# 555TimerOrganFinal.net
KiCad netlist of a schematic drawn in Altium Designer
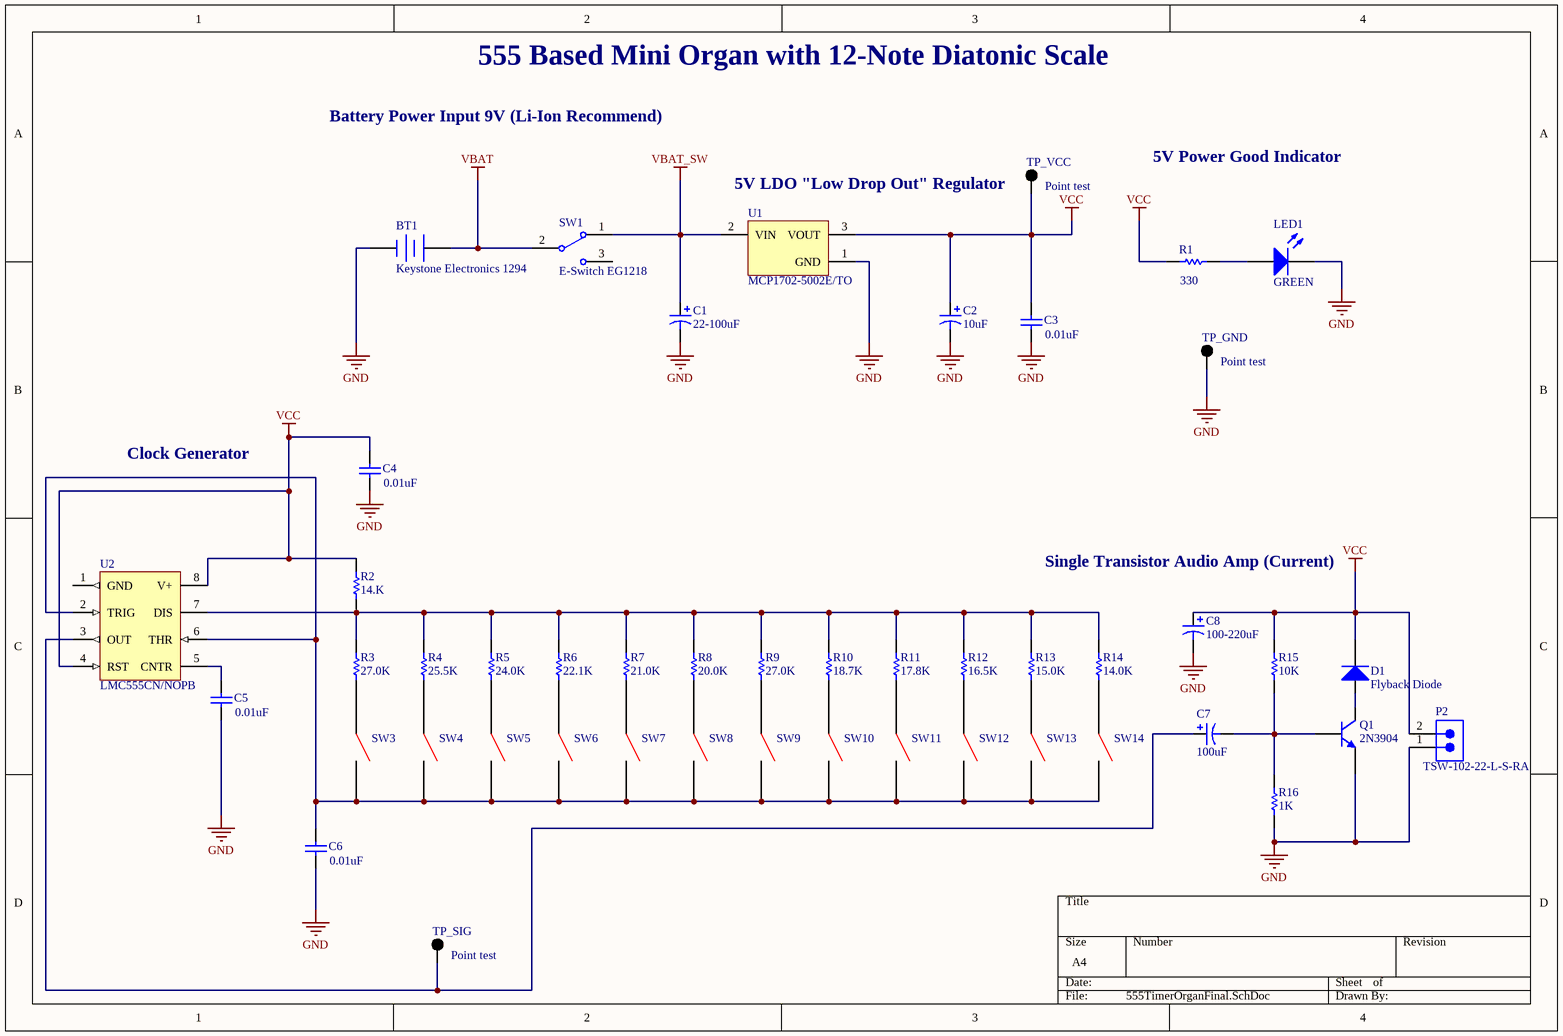
[diagram p0: 555TimerOrganFinal.SchDoc]

(export (version "E")
  (design (tool "Eeschema 10.0.6"))
  (components
    (comp (ref "BT1")
      (value "Keystone Electronics 1294")
      (footprint "PCB-3798-1")
      (description "HOLDER BATT 9V UNIV PLASTIC PC")
      (fields (field (name "MANUFACTURER PART NUMBER") "1294"))
      (libsource (lib "My Personal Space") (part "SYM-3798-1"))
    )
    (comp (ref "C1")
      (value "22-100uF")
      (footprint "PCB-nq6yd78wv7rl8ojp8omb-1")
      (description "Cap Aluminum 10uF 16V 20% (4 X 7mm) Cylindrical 18mA 7000 hr 105°C T/R")
      (fields (field (name "MANUFACTURER PART NUMBER") "UCB1C100MCL1GS"))
      (libsource (lib "My Personal Space") (part "SYM-119dd9bbe86bce5a-1"))
    )
    (comp (ref "C2")
      (value "10uF")
      (footprint "PCB-nq6yd78wv7rl8ojp8omb-1")
      (description "Cap Aluminum 10uF 16V 20% (4 X 7mm) Cylindrical 18mA 7000 hr 105°C T/R")
      (fields (field (name "MANUFACTURER PART NUMBER") "UCB1C100MCL1GS"))
      (libsource (lib "My Personal Space") (part "SYM-119dd9bbe86bce5a-1"))
    )
    (comp (ref "C3")
      (value "0.01uF")
      (footprint "PCB-ql28fbuo3tond8refhb5-1")
      (description "K 100nF Ceramic Multilayer Capacitor, 50 V dc, +125degC, X7R Dielectric, +/-10%")
      (libsource (lib "My Personal Space") (part "SYM-1272d9258f2acdb5-2"))
    )
    (comp (ref "C4")
      (value "0.01uF")
      (footprint "PCB-ql28fbuo3tond8refhb5-1")
      (description "K 100nF Ceramic Multilayer Capacitor, 50 V dc, +125degC, X7R Dielectric, +/-10%")
      (libsource (lib "My Personal Space") (part "SYM-1272d9258f2acdb5-2"))
    )
    (comp (ref "C5")
      (value "0.01uF")
      (footprint "PCB-ql28fbuo3tond8refhb5-1")
      (description "K 100nF Ceramic Multilayer Capacitor, 50 V dc, +125degC, X7R Dielectric, +/-10%")
      (libsource (lib "My Personal Space") (part "SYM-1272d9258f2acdb5-2"))
    )
    (comp (ref "C6")
      (value "0.01uF")
      (footprint "PCB-ql28fbuo3tond8refhb5-1")
      (description "K 100nF Ceramic Multilayer Capacitor, 50 V dc, +125degC, X7R Dielectric, +/-10%")
      (libsource (lib "My Personal Space") (part "SYM-1272d9258f2acdb5-2"))
    )
    (comp (ref "C7")
      (value "100uF")
      (footprint "PCB-nq6yd78wv7rl8ojp8omb-1")
      (description "Cap Aluminum 10uF 16V 20% (4 X 7mm) Cylindrical 18mA 7000 hr 105°C T/R")
      (fields (field (name "MANUFACTURER PART NUMBER") "UCB1C100MCL1GS"))
      (libsource (lib "My Personal Space") (part "SYM-119dd9bbe86bce5a-1"))
    )
    (comp (ref "C8")
      (value "100-220uF")
      (footprint "PCB-nq6yd78wv7rl8ojp8omb-1")
      (description "Cap Aluminum 10uF 16V 20% (4 X 7mm) Cylindrical 18mA 7000 hr 105°C T/R")
      (fields (field (name "MANUFACTURER PART NUMBER") "UCB1C100MCL1GS"))
      (libsource (lib "My Personal Space") (part "SYM-119dd9bbe86bce5a-1"))
    )
    (comp (ref "D1")
      (value "Flyback Diode")
      (footprint "PCB-z2ypi7zr74mzpyjelpsh-1")
      (description "Standard Recovery Rectifier, 2-Pin Axial_Lead, Pb-Free, Tape and Reel")
      (fields (field (name "MANUFACTURER PART NUMBER") "1N4001RLG"))
      (libsource (lib "My Personal Space") (part "SYM-e02d2927e6e83fea-1"))
    )
    (comp (ref "LED1")
      (value "GREEN")
      (footprint "PCB-b5vk7vz0xhkw7l0fnova-1")
      (description "LED Uni-Color Green 2-Pin T-1 3/4 Bulk")
      (fields
        (field (name "MANUFACTURER PART NUMBER") "C503B-GCN-CY0C0791")
        (field (name "MANUFACTURER") "Cree")
      )
      (libsource (lib "My Personal Space") (part "SYM-92bb5b2eff764d7c-1"))
    )
    (comp (ref "P2")
      (value "TSW-102-22-L-S-RA")
      (footprint "SMTC-TSW-102-22-X-S-RA")
      (libsource (lib "My Personal Space") (part "SMTC-TSW-102-X-X-S-X"))
    )
    (comp (ref "Q1")
      (value "2N3904")
      (footprint "PCB-d52vzgbszc9onplxz1b0-1")
      (description "Transistor General Purpose BJT NPN 40 Volt 0.2 Amp 3-Pin TO-92 Tape And Reel")
      (fields (field (name "MANUFACTURER PART NUMBER") "2N3904TF"))
      (libsource (lib "My Personal Space") (part "2N3904"))
    )
    (comp (ref "R1")
      (value "330")
      (footprint "PCB-0jk5y5qyb1smy9vf6b7t-1")
      (description "Res, 1K, 250mW, 5%, Axial")
      (libsource (lib "My Personal Space") (part "SYM-db3e1311f37e04f9-4"))
    )
    (comp (ref "R2")
      (value "14.K")
      (footprint "PCB-0jk5y5qyb1smy9vf6b7t-1")
      (description "Res, 1K, 250mW, 5%, Axial")
      (libsource (lib "My Personal Space") (part "SYM-db3e1311f37e04f9-4"))
    )
    (comp (ref "R3")
      (value "27.0K")
      (footprint "PCB-0jk5y5qyb1smy9vf6b7t-1")
      (description "Res, 1K, 250mW, 5%, Axial")
      (libsource (lib "My Personal Space") (part "SYM-db3e1311f37e04f9-4"))
    )
    (comp (ref "R4")
      (value "25.5K")
      (footprint "PCB-0jk5y5qyb1smy9vf6b7t-1")
      (description "Res, 1K, 250mW, 5%, Axial")
      (libsource (lib "My Personal Space") (part "SYM-db3e1311f37e04f9-4"))
    )
    (comp (ref "R5")
      (value "24.0K")
      (footprint "PCB-0jk5y5qyb1smy9vf6b7t-1")
      (description "Res, 1K, 250mW, 5%, Axial")
      (libsource (lib "My Personal Space") (part "SYM-db3e1311f37e04f9-4"))
    )
    (comp (ref "R6")
      (value "22.1K")
      (footprint "PCB-0jk5y5qyb1smy9vf6b7t-1")
      (description "Res, 1K, 250mW, 5%, Axial")
      (libsource (lib "My Personal Space") (part "SYM-db3e1311f37e04f9-4"))
    )
    (comp (ref "R7")
      (value "21.0K")
      (footprint "PCB-0jk5y5qyb1smy9vf6b7t-1")
      (description "Res, 1K, 250mW, 5%, Axial")
      (libsource (lib "My Personal Space") (part "SYM-db3e1311f37e04f9-4"))
    )
    (comp (ref "R8")
      (value "20.0K")
      (footprint "PCB-0jk5y5qyb1smy9vf6b7t-1")
      (description "Res, 1K, 250mW, 5%, Axial")
      (libsource (lib "My Personal Space") (part "SYM-db3e1311f37e04f9-4"))
    )
    (comp (ref "R9")
      (value "27.0K")
      (footprint "PCB-0jk5y5qyb1smy9vf6b7t-1")
      (description "Res, 1K, 250mW, 5%, Axial")
      (libsource (lib "My Personal Space") (part "SYM-db3e1311f37e04f9-4"))
    )
    (comp (ref "R10")
      (value "18.7K")
      (footprint "PCB-0jk5y5qyb1smy9vf6b7t-1")
      (description "Res, 1K, 250mW, 5%, Axial")
      (libsource (lib "My Personal Space") (part "SYM-db3e1311f37e04f9-4"))
    )
    (comp (ref "R11")
      (value "17.8K")
      (footprint "PCB-0jk5y5qyb1smy9vf6b7t-1")
      (description "Res, 1K, 250mW, 5%, Axial")
      (libsource (lib "My Personal Space") (part "SYM-db3e1311f37e04f9-4"))
    )
    (comp (ref "R12")
      (value "16.5K")
      (footprint "PCB-0jk5y5qyb1smy9vf6b7t-1")
      (description "Res, 1K, 250mW, 5%, Axial")
      (libsource (lib "My Personal Space") (part "SYM-db3e1311f37e04f9-4"))
    )
    (comp (ref "R13")
      (value "15.0K")
      (footprint "PCB-0jk5y5qyb1smy9vf6b7t-1")
      (description "Res, 1K, 250mW, 5%, Axial")
      (libsource (lib "My Personal Space") (part "SYM-db3e1311f37e04f9-4"))
    )
    (comp (ref "R14")
      (value "14.0K")
      (footprint "PCB-0jk5y5qyb1smy9vf6b7t-1")
      (description "Res, 1K, 250mW, 5%, Axial")
      (libsource (lib "My Personal Space") (part "SYM-db3e1311f37e04f9-4"))
    )
    (comp (ref "R15")
      (value "10K")
      (footprint "PCB-0jk5y5qyb1smy9vf6b7t-1")
      (description "Res, 1K, 250mW, 5%, Axial")
      (libsource (lib "My Personal Space") (part "SYM-db3e1311f37e04f9-4"))
    )
    (comp (ref "R16")
      (value "1K")
      (footprint "PCB-0jk5y5qyb1smy9vf6b7t-1")
      (description "Res, 1K, 250mW, 5%, Axial")
      (libsource (lib "My Personal Space") (part "SYM-db3e1311f37e04f9-4"))
    )
    (comp (ref "SW1")
      (value "E-Switch EG1218")
      (footprint "ESWI-EG1218_V")
      (description "Slide Switch, 500 V, -20 to 70 degC, 3-Pin THD, RoHS")
      (fields (field (name "MANUFACTURER PART NUMBER") "EG1218"))
      (libsource (lib "My Personal Space") (part "SW-SPDT-3_B"))
    )
    (comp (ref "SW3")
      (value "~")
      (footprint "PCB-je10m8m3eogq13l465bo-1")
      (description "Switch Tactile N.O. SPST Round Button PC Pins 0.02A 15VDC 1.3N Thru-Hole Radial T/R")
      (fields
        (field (name "ELEMENT14 PART NO.") "2281982")
        (field (name "MANUFACTURER PART NUMBER") "EVQ-21405R")
      )
      (libsource (lib "My Personal Space") (part "SYM-2fe5e5be239cf022-1"))
    )
    (comp (ref "SW4")
      (value "~")
      (footprint "PCB-je10m8m3eogq13l465bo-1")
      (description "Switch Tactile N.O. SPST Round Button PC Pins 0.02A 15VDC 1.3N Thru-Hole Radial T/R")
      (fields
        (field (name "ELEMENT14 PART NO.") "2281982")
        (field (name "MANUFACTURER PART NUMBER") "EVQ-21405R")
      )
      (libsource (lib "My Personal Space") (part "SYM-2fe5e5be239cf022-1"))
    )
    (comp (ref "SW5")
      (value "~")
      (footprint "PCB-je10m8m3eogq13l465bo-1")
      (description "Switch Tactile N.O. SPST Round Button PC Pins 0.02A 15VDC 1.3N Thru-Hole Radial T/R")
      (fields
        (field (name "ELEMENT14 PART NO.") "2281982")
        (field (name "MANUFACTURER PART NUMBER") "EVQ-21405R")
      )
      (libsource (lib "My Personal Space") (part "SYM-2fe5e5be239cf022-1"))
    )
    (comp (ref "SW6")
      (value "~")
      (footprint "PCB-je10m8m3eogq13l465bo-1")
      (description "Switch Tactile N.O. SPST Round Button PC Pins 0.02A 15VDC 1.3N Thru-Hole Radial T/R")
      (fields
        (field (name "ELEMENT14 PART NO.") "2281982")
        (field (name "MANUFACTURER PART NUMBER") "EVQ-21405R")
      )
      (libsource (lib "My Personal Space") (part "SYM-2fe5e5be239cf022-1"))
    )
    (comp (ref "SW7")
      (value "~")
      (footprint "PCB-je10m8m3eogq13l465bo-1")
      (description "Switch Tactile N.O. SPST Round Button PC Pins 0.02A 15VDC 1.3N Thru-Hole Radial T/R")
      (fields
        (field (name "ELEMENT14 PART NO.") "2281982")
        (field (name "MANUFACTURER PART NUMBER") "EVQ-21405R")
      )
      (libsource (lib "My Personal Space") (part "SYM-2fe5e5be239cf022-1"))
    )
    (comp (ref "SW8")
      (value "~")
      (footprint "PCB-je10m8m3eogq13l465bo-1")
      (description "Switch Tactile N.O. SPST Round Button PC Pins 0.02A 15VDC 1.3N Thru-Hole Radial T/R")
      (fields
        (field (name "ELEMENT14 PART NO.") "2281982")
        (field (name "MANUFACTURER PART NUMBER") "EVQ-21405R")
      )
      (libsource (lib "My Personal Space") (part "SYM-2fe5e5be239cf022-1"))
    )
    (comp (ref "SW9")
      (value "~")
      (footprint "PCB-je10m8m3eogq13l465bo-1")
      (description "Switch Tactile N.O. SPST Round Button PC Pins 0.02A 15VDC 1.3N Thru-Hole Radial T/R")
      (fields
        (field (name "ELEMENT14 PART NO.") "2281982")
        (field (name "MANUFACTURER PART NUMBER") "EVQ-21405R")
      )
      (libsource (lib "My Personal Space") (part "SYM-2fe5e5be239cf022-1"))
    )
    (comp (ref "SW10")
      (value "~")
      (footprint "PCB-je10m8m3eogq13l465bo-1")
      (description "Switch Tactile N.O. SPST Round Button PC Pins 0.02A 15VDC 1.3N Thru-Hole Radial T/R")
      (fields
        (field (name "ELEMENT14 PART NO.") "2281982")
        (field (name "MANUFACTURER PART NUMBER") "EVQ-21405R")
      )
      (libsource (lib "My Personal Space") (part "SYM-2fe5e5be239cf022-1"))
    )
    (comp (ref "SW11")
      (value "~")
      (footprint "PCB-je10m8m3eogq13l465bo-1")
      (description "Switch Tactile N.O. SPST Round Button PC Pins 0.02A 15VDC 1.3N Thru-Hole Radial T/R")
      (fields
        (field (name "ELEMENT14 PART NO.") "2281982")
        (field (name "MANUFACTURER PART NUMBER") "EVQ-21405R")
      )
      (libsource (lib "My Personal Space") (part "SYM-2fe5e5be239cf022-1"))
    )
    (comp (ref "SW12")
      (value "~")
      (footprint "PCB-je10m8m3eogq13l465bo-1")
      (description "Switch Tactile N.O. SPST Round Button PC Pins 0.02A 15VDC 1.3N Thru-Hole Radial T/R")
      (fields
        (field (name "ELEMENT14 PART NO.") "2281982")
        (field (name "MANUFACTURER PART NUMBER") "EVQ-21405R")
      )
      (libsource (lib "My Personal Space") (part "SYM-2fe5e5be239cf022-1"))
    )
    (comp (ref "SW13")
      (value "~")
      (footprint "PCB-je10m8m3eogq13l465bo-1")
      (description "Switch Tactile N.O. SPST Round Button PC Pins 0.02A 15VDC 1.3N Thru-Hole Radial T/R")
      (fields
        (field (name "ELEMENT14 PART NO.") "2281982")
        (field (name "MANUFACTURER PART NUMBER") "EVQ-21405R")
      )
      (libsource (lib "My Personal Space") (part "SYM-2fe5e5be239cf022-1"))
    )
    (comp (ref "SW14")
      (value "~")
      (footprint "PCB-je10m8m3eogq13l465bo-1")
      (description "Switch Tactile N.O. SPST Round Button PC Pins 0.02A 15VDC 1.3N Thru-Hole Radial T/R")
      (fields
        (field (name "ELEMENT14 PART NO.") "2281982")
        (field (name "MANUFACTURER PART NUMBER") "EVQ-21405R")
      )
      (libsource (lib "My Personal Space") (part "SYM-2fe5e5be239cf022-1"))
    )
    (comp (ref "TP_GND")
      (value "Point test")
      (footprint "P1-09")
      (description "KEYSTONE   5001   TEST POINT, PCB, THROUGH HOLE")
      (libsource (lib "My Personal Space") (part "KSTN-5001"))
    )
    (comp (ref "TP_SIG")
      (value "Point test")
      (footprint "P1-09")
      (description "KEYSTONE   5001   TEST POINT, PCB, THROUGH HOLE")
      (libsource (lib "My Personal Space") (part "KSTN-5001"))
    )
    (comp (ref "TP_VCC")
      (value "Point test")
      (footprint "P1-09")
      (description "KEYSTONE   5001   TEST POINT, PCB, THROUGH HOLE")
      (libsource (lib "My Personal Space") (part "KSTN-5001"))
    )
    (comp (ref "U1")
      (value "MCP1702-5002E/TO")
      (footprint "TO-92-TO3")
      (description "250 mA Low Quiescent Current LDO Regulator, 3-Pin TO-92, Extended TemperatureBAG")
      (libsource (lib "My Personal Space") (part "PM-LINEREG-MCP1702-IL3A"))
    )
    (comp (ref "U2")
      (value "LMC555CN/NOPB")
      (footprint "TI-D8_L")
      (description "World’s smallest 555 timer with low power, high accuracy and a Fmax of 3MHz 8-SOIC -40 to 85")
      (fields (field (name "MANUFACTURER PART NUMBER") "LMC555CMX/NOPB"))
      (libsource (lib "My Personal Space") (part "INF-TLE5012BE5000-PG-DSO-8-16-8"))
    )
  )
  (nets
    (net (code "1") (name "GND") (class "Default")
      (node (ref "BT1") (pin "2") (pinfunction "-_2") (pintype "passive"))
      (node (ref "C1") (pin "2") (pinfunction "2_2") (pintype "passive"))
      (node (ref "C2") (pin "2") (pinfunction "2_2") (pintype "passive"))
      (node (ref "C3") (pin "1") (pinfunction "1_1") (pintype "passive"))
      (node (ref "C4") (pin "1") (pinfunction "1_1") (pintype "passive"))
      (node (ref "C5") (pin "1") (pinfunction "1_1") (pintype "passive"))
      (node (ref "C6") (pin "1") (pinfunction "1_1") (pintype "passive"))
      (node (ref "C8") (pin "2") (pinfunction "2_2") (pintype "passive"))
      (node (ref "LED1") (pin "1") (pinfunction "K_1") (pintype "passive"))
      (node (ref "P2") (pin "1") (pinfunction "1_1") (pintype "passive"))
      (node (ref "Q1") (pin "E") (pinfunction "E_E") (pintype "passive"))
      (node (ref "R16") (pin "2") (pinfunction "2_2") (pintype "passive"))
      (node (ref "TP_GND") (pin "1") (pinfunction "1_1") (pintype "passive"))
      (node (ref "U1") (pin "1") (pinfunction "GND_1") (pintype "power_in"))
    )
    (net (code "2") (name "Net-(C7-Pad2)") (class "Default")
      (node (ref "C7") (pin "2") (pinfunction "2_2") (pintype "passive"))
      (node (ref "Q1") (pin "B") (pinfunction "B_B") (pintype "passive"))
      (node (ref "R15") (pin "2") (pinfunction "2_2") (pintype "passive"))
      (node (ref "R16") (pin "1") (pinfunction "1_1") (pintype "passive"))
    )
    (net (code "3") (name "Net-(D1-A)") (class "Default")
      (node (ref "D1") (pin "1") (pinfunction "A_1") (pintype "passive"))
      (node (ref "Q1") (pin "C") (pinfunction "C_C") (pintype "passive"))
    )
    (net (code "4") (name "Net-(LED1-A)") (class "Default")
      (node (ref "LED1") (pin "2") (pinfunction "A_2") (pintype "passive"))
      (node (ref "R1") (pin "2") (pinfunction "2_2") (pintype "passive"))
    )
    (net (code "5") (name "Net-(R3-Pad2)") (class "Default")
      (node (ref "R3") (pin "2") (pinfunction "2_2") (pintype "passive"))
      (node (ref "SW3") (pin "1") (pinfunction "1_1") (pintype "passive"))
    )
    (net (code "6") (name "Net-(R4-Pad2)") (class "Default")
      (node (ref "R4") (pin "2") (pinfunction "2_2") (pintype "passive"))
      (node (ref "SW4") (pin "1") (pinfunction "1_1") (pintype "passive"))
    )
    (net (code "7") (name "Net-(R5-Pad2)") (class "Default")
      (node (ref "R5") (pin "2") (pinfunction "2_2") (pintype "passive"))
      (node (ref "SW5") (pin "1") (pinfunction "1_1") (pintype "passive"))
    )
    (net (code "8") (name "Net-(R6-Pad2)") (class "Default")
      (node (ref "R6") (pin "2") (pinfunction "2_2") (pintype "passive"))
      (node (ref "SW6") (pin "1") (pinfunction "1_1") (pintype "passive"))
    )
    (net (code "9") (name "Net-(R7-Pad2)") (class "Default")
      (node (ref "R7") (pin "2") (pinfunction "2_2") (pintype "passive"))
      (node (ref "SW7") (pin "1") (pinfunction "1_1") (pintype "passive"))
    )
    (net (code "10") (name "Net-(R8-Pad2)") (class "Default")
      (node (ref "R8") (pin "2") (pinfunction "2_2") (pintype "passive"))
      (node (ref "SW8") (pin "1") (pinfunction "1_1") (pintype "passive"))
    )
    (net (code "11") (name "Net-(R9-Pad2)") (class "Default")
      (node (ref "R9") (pin "2") (pinfunction "2_2") (pintype "passive"))
      (node (ref "SW9") (pin "1") (pinfunction "1_1") (pintype "passive"))
    )
    (net (code "12") (name "Net-(R10-Pad2)") (class "Default")
      (node (ref "R10") (pin "2") (pinfunction "2_2") (pintype "passive"))
      (node (ref "SW10") (pin "1") (pinfunction "1_1") (pintype "passive"))
    )
    (net (code "13") (name "Net-(R11-Pad2)") (class "Default")
      (node (ref "R11") (pin "2") (pinfunction "2_2") (pintype "passive"))
      (node (ref "SW11") (pin "1") (pinfunction "1_1") (pintype "passive"))
    )
    (net (code "14") (name "Net-(R12-Pad2)") (class "Default")
      (node (ref "R12") (pin "2") (pinfunction "2_2") (pintype "passive"))
      (node (ref "SW12") (pin "1") (pinfunction "1_1") (pintype "passive"))
    )
    (net (code "15") (name "Net-(R13-Pad2)") (class "Default")
      (node (ref "R13") (pin "2") (pinfunction "2_2") (pintype "passive"))
      (node (ref "SW13") (pin "1") (pinfunction "1_1") (pintype "passive"))
    )
    (net (code "16") (name "Net-(R14-Pad2)") (class "Default")
      (node (ref "R14") (pin "2") (pinfunction "2_2") (pintype "passive"))
      (node (ref "SW14") (pin "1") (pinfunction "1_1") (pintype "passive"))
    )
    (net (code "17") (name "Net-(U2-CNTR)") (class "Default")
      (node (ref "C5") (pin "2") (pinfunction "2_2") (pintype "passive"))
      (node (ref "U2") (pin "5") (pinfunction "CNTR_5") (pintype "passive"))
    )
    (net (code "18") (name "Net-(U2-DIS)") (class "Default")
      (node (ref "R10") (pin "1") (pinfunction "1_1") (pintype "passive"))
      (node (ref "R11") (pin "1") (pinfunction "1_1") (pintype "passive"))
      (node (ref "R12") (pin "1") (pinfunction "1_1") (pintype "passive"))
      (node (ref "R13") (pin "1") (pinfunction "1_1") (pintype "passive"))
      (node (ref "R14") (pin "1") (pinfunction "1_1") (pintype "passive"))
      (node (ref "R2") (pin "2") (pinfunction "2_2") (pintype "passive"))
      (node (ref "R3") (pin "1") (pinfunction "1_1") (pintype "passive"))
      (node (ref "R4") (pin "1") (pinfunction "1_1") (pintype "passive"))
      (node (ref "R5") (pin "1") (pinfunction "1_1") (pintype "passive"))
      (node (ref "R6") (pin "1") (pinfunction "1_1") (pintype "passive"))
      (node (ref "R7") (pin "1") (pinfunction "1_1") (pintype "passive"))
      (node (ref "R8") (pin "1") (pinfunction "1_1") (pintype "passive"))
      (node (ref "R9") (pin "1") (pinfunction "1_1") (pintype "passive"))
      (node (ref "U2") (pin "7") (pinfunction "DIS_7") (pintype "passive"))
    )
    (net (code "19") (name "Net-(U2-OUT)") (class "Default")
      (node (ref "C7") (pin "1") (pinfunction "1_1") (pintype "passive"))
      (node (ref "TP_SIG") (pin "1") (pinfunction "1_1") (pintype "passive"))
      (node (ref "U2") (pin "3") (pinfunction "OUT_3") (pintype "output"))
    )
    (net (code "20") (name "Net-(U2-THR)") (class "Default")
      (node (ref "C6") (pin "2") (pinfunction "2_2") (pintype "passive"))
      (node (ref "SW10") (pin "2") (pinfunction "2_2") (pintype "passive"))
      (node (ref "SW11") (pin "2") (pinfunction "2_2") (pintype "passive"))
      (node (ref "SW12") (pin "2") (pinfunction "2_2") (pintype "passive"))
      (node (ref "SW13") (pin "2") (pinfunction "2_2") (pintype "passive"))
      (node (ref "SW14") (pin "2") (pinfunction "2_2") (pintype "passive"))
      (node (ref "SW3") (pin "2") (pinfunction "2_2") (pintype "passive"))
      (node (ref "SW4") (pin "2") (pinfunction "2_2") (pintype "passive"))
      (node (ref "SW5") (pin "2") (pinfunction "2_2") (pintype "passive"))
      (node (ref "SW6") (pin "2") (pinfunction "2_2") (pintype "passive"))
      (node (ref "SW7") (pin "2") (pinfunction "2_2") (pintype "passive"))
      (node (ref "SW8") (pin "2") (pinfunction "2_2") (pintype "passive"))
      (node (ref "SW9") (pin "2") (pinfunction "2_2") (pintype "passive"))
      (node (ref "U2") (pin "2") (pinfunction "TRIG_2") (pintype "input"))
      (node (ref "U2") (pin "6") (pinfunction "THR_6") (pintype "input"))
    )
    (net (code "21") (name "VBAT") (class "Default")
      (node (ref "BT1") (pin "1") (pinfunction "+_1") (pintype "passive"))
      (node (ref "SW1") (pin "2") (pinfunction "COM_2") (pintype "passive"))
    )
    (net (code "22") (name "VBAT_SW") (class "Default")
      (node (ref "C1") (pin "1") (pinfunction "1_1") (pintype "passive"))
      (node (ref "SW1") (pin "1") (pinfunction "1_1") (pintype "passive"))
      (node (ref "U1") (pin "2") (pinfunction "VIN_2") (pintype "power_in"))
    )
    (net (code "23") (name "VCC") (class "Default")
      (node (ref "C2") (pin "1") (pinfunction "1_1") (pintype "passive"))
      (node (ref "C3") (pin "2") (pinfunction "2_2") (pintype "passive"))
      (node (ref "C4") (pin "2") (pinfunction "2_2") (pintype "passive"))
      (node (ref "C8") (pin "1") (pinfunction "1_1") (pintype "passive"))
      (node (ref "D1") (pin "2") (pinfunction "K_2") (pintype "passive"))
      (node (ref "P2") (pin "2") (pinfunction "2_2") (pintype "passive"))
      (node (ref "R1") (pin "1") (pinfunction "1_1") (pintype "passive"))
      (node (ref "R15") (pin "1") (pinfunction "1_1") (pintype "passive"))
      (node (ref "R2") (pin "1") (pinfunction "1_1") (pintype "passive"))
      (node (ref "TP_VCC") (pin "1") (pinfunction "1_1") (pintype "passive"))
      (node (ref "U1") (pin "3") (pinfunction "VOUT_3") (pintype "power_in"))
      (node (ref "U2") (pin "4") (pinfunction "RST_4") (pintype "input"))
      (node (ref "U2") (pin "8") (pinfunction "V+_8") (pintype "power_in"))
    )
    (net (code "24") (name "unconnected-(SW1-Pad3)") (class "Default")
      (node (ref "SW1") (pin "3") (pinfunction "3_3") (pintype "passive"))
    )
    (net (code "25") (name "unconnected-(U2-GND-Pad1)") (class "Default")
      (node (ref "U2") (pin "1") (pinfunction "GND_1") (pintype "output"))
    )
  )
)
